# USBDUINO_DIP_SCH.net
KiCad netlist of a schematic drawn in EAGLE
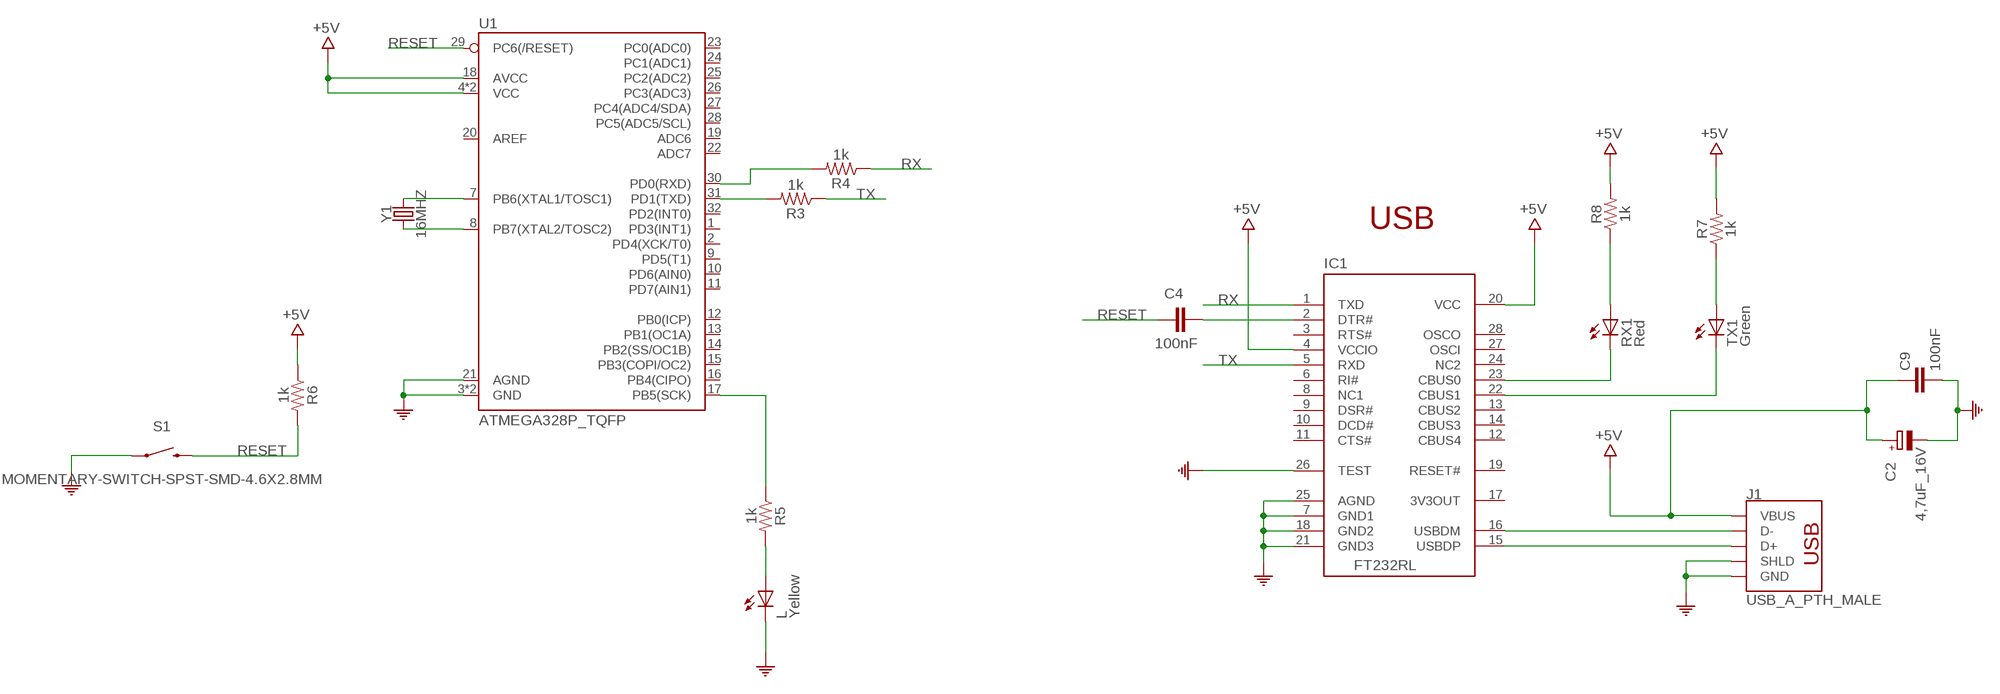
[diagram p0: schematic, sheet 1]

(export (version "E")
  (design (tool "Eeschema 10.0.6"))
  (components
    (comp (ref "C2")
      (value "4,7uF_16V")
      (footprint "eagle-import:TAN-A")
      (fields (field (name "PART_NUMBER") "TAJA475MO16RNJ"))
      (libsource (lib "eagle-import") (part "0833_TAJA475MO16RNJ"))
    )
    (comp (ref "C4")
      (value "100nF")
      (footprint "eagle-import:C0603-ROUND")
      (fields (field (name "PART_NUMBER") "cl10b104kbnc"))
      (libsource (lib "eagle-import") (part "0015_100NF_0603"))
    )
    (comp (ref "C9")
      (value "100nF")
      (footprint "eagle-import:C0603-ROUND")
      (fields (field (name "PART_NUMBER") "cl10b104kbnc"))
      (libsource (lib "eagle-import") (part "0015_100NF_0603"))
    )
    (comp (ref "IC1")
      (value "FT232RL")
      (footprint "eagle-import:SSOP28")
      (libsource (lib "eagle-import") (part "0226_FT232RL"))
    )
    (comp (ref "J1")
      (value "USB_A_PTH_MALE")
      (footprint "eagle-import:USB-A-H")
      (libsource (lib "eagle-import") (part "USB_A_PTH_MALE"))
    )
    (comp (ref "L")
      (value "Yellow")
      (footprint "eagle-import:CHIPLED_0805")
      (fields (field (name "PART_NUMBER") "KPT-2012YC"))
      (libsource (lib "eagle-import") (part "0044_KPT-2012YC"))
    )
    (comp (ref "R3")
      (value "1k")
      (footprint "eagle-import:0603")
      (libsource (lib "eagle-import") (part "1KOHM-0603-1/10W-1%"))
    )
    (comp (ref "R4")
      (value "1k")
      (footprint "eagle-import:0603")
      (libsource (lib "eagle-import") (part "1KOHM-0603-1/10W-1%"))
    )
    (comp (ref "R5")
      (value "1k")
      (footprint "eagle-import:0603")
      (libsource (lib "eagle-import") (part "1KOHM-0603-1/10W-1%"))
    )
    (comp (ref "R6")
      (value "1k")
      (footprint "eagle-import:0603")
      (libsource (lib "eagle-import") (part "1KOHM-0603-1/10W-1%"))
    )
    (comp (ref "R7")
      (value "1k")
      (footprint "eagle-import:0603")
      (libsource (lib "eagle-import") (part "1KOHM-0603-1/10W-1%"))
    )
    (comp (ref "R8")
      (value "1k")
      (footprint "eagle-import:0603")
      (libsource (lib "eagle-import") (part "1KOHM-0603-1/10W-1%"))
    )
    (comp (ref "RX1")
      (value "Red")
      (footprint "eagle-import:CHIPLED_0805")
      (fields (field (name "PART_NUMBER") "KTP-2012SURCK"))
      (libsource (lib "eagle-import") (part "0181_KTP-2012SURCK"))
    )
    (comp (ref "S1")
      (value "MOMENTARY-SWITCH-SPST-SMD-4.6X2.8MM")
      (footprint "eagle-import:TACTILE_SWITCH_SMD_4.6X2.8MM")
      (libsource (lib "eagle-import") (part "MOMENTARY-SWITCH-SPST-SMD-4.6X2.8MM"))
    )
    (comp (ref "TX1")
      (value "Green")
      (footprint "eagle-import:CHIPLED_0805")
      (fields (field (name "PART_NUMBER") "KPT-2012SGC"))
      (libsource (lib "eagle-import") (part "0043_KPT-2012SGC"))
    )
    (comp (ref "U1")
      (value "ATMEGA328P_TQFP")
      (footprint "eagle-import:TQFP32-08")
      (libsource (lib "eagle-import") (part "ATMEGA328P_TQFP"))
    )
    (comp (ref "Y1")
      (value "16MHZ")
      (footprint "eagle-import:HC49UP")
      (libsource (lib "eagle-import") (part "CRYSTALSMD-HC49UP"))
    )
  )
  (nets
    (net (code "1") (name "+5V") (class "Default")
      (node (ref "C2") (pin "1") (pinfunction "+_1") (pintype "passive"))
      (node (ref "C9") (pin "1") (pinfunction "1_1") (pintype "passive"))
      (node (ref "IC1") (pin "20") (pinfunction "VCC_20") (pintype "power_in"))
      (node (ref "IC1") (pin "4") (pinfunction "VCCIO_4") (pintype "power_in"))
      (node (ref "J1") (pin "VBUS") (pinfunction "VBUS_VBUS") (pintype "power_in"))
      (node (ref "R6") (pin "1") (pinfunction "1_1") (pintype "passive"))
      (node (ref "R7") (pin "2") (pinfunction "2_2") (pintype "passive"))
      (node (ref "R8") (pin "2") (pinfunction "2_2") (pintype "passive"))
      (node (ref "U1") (pin "18") (pinfunction "AVCC_18") (pintype "bidirectional"))
      (node (ref "U1") (pin "4") (pinfunction "VCC_4") (pintype "bidirectional"))
      (node (ref "U1") (pin "6") (pinfunction "VCC_6") (pintype "bidirectional"))
    )
    (net (code "2") (name "/3V3OUT") (class "Default")
      (node (ref "IC1") (pin "17") (pinfunction "3V3OUT_17") (pintype "power_in"))
    )
    (net (code "3") (name "/RESET") (class "Default")
      (node (ref "C4") (pin "1") (pinfunction "1_1") (pintype "passive"))
      (node (ref "R6") (pin "2") (pinfunction "2_2") (pintype "passive"))
      (node (ref "S1") (pin "3") (pinfunction "2_3") (pintype "passive"))
      (node (ref "S1") (pin "4") (pinfunction "2_4") (pintype "passive"))
      (node (ref "U1") (pin "29") (pinfunction "PC6(/RESET)_29") (pintype "bidirectional"))
    )
    (net (code "4") (name "/RX") (class "Default")
      (node (ref "IC1") (pin "1") (pinfunction "TXD_1") (pintype "output"))
      (node (ref "R4") (pin "1") (pinfunction "1_1") (pintype "passive"))
    )
    (net (code "5") (name "/TX") (class "Default")
      (node (ref "IC1") (pin "5") (pinfunction "RXD_5") (pintype "input"))
      (node (ref "R3") (pin "1") (pinfunction "1_1") (pintype "passive"))
    )
    (net (code "6") (name "COM") (class "Default")
      (node (ref "C2") (pin "2") (pinfunction "-_2") (pintype "passive"))
      (node (ref "C9") (pin "2") (pinfunction "2_2") (pintype "passive"))
      (node (ref "IC1") (pin "18") (pinfunction "GND2_18") (pintype "power_in"))
      (node (ref "IC1") (pin "21") (pinfunction "GND3_21") (pintype "power_in"))
      (node (ref "IC1") (pin "25") (pinfunction "AGND_25") (pintype "power_in"))
      (node (ref "IC1") (pin "26") (pinfunction "TEST_26") (pintype "bidirectional"))
      (node (ref "IC1") (pin "7") (pinfunction "GND1_7") (pintype "power_in"))
      (node (ref "J1") (pin "GND") (pinfunction "GND_GND") (pintype "power_in"))
      (node (ref "J1") (pin "SHLD1") (pinfunction "SHLD_SHLD1") (pintype "bidirectional"))
      (node (ref "J1") (pin "SHLD2") (pinfunction "SHLD_SHLD2") (pintype "bidirectional"))
      (node (ref "L") (pin "C") (pinfunction "C_C") (pintype "passive"))
      (node (ref "S1") (pin "1") (pinfunction "1_1") (pintype "passive"))
      (node (ref "S1") (pin "2") (pinfunction "1_2") (pintype "passive"))
      (node (ref "U1") (pin "21") (pinfunction "AGND_21") (pintype "bidirectional"))
      (node (ref "U1") (pin "3") (pinfunction "GND_3") (pintype "bidirectional"))
      (node (ref "U1") (pin "5") (pinfunction "GND_5") (pintype "bidirectional"))
    )
    (net (code "7") (name "Net-(IC1-CBUS0)") (class "Default")
      (node (ref "IC1") (pin "23") (pinfunction "CBUS0_23") (pintype "bidirectional"))
      (node (ref "RX1") (pin "C") (pinfunction "C_C") (pintype "passive"))
    )
    (net (code "8") (name "Net-(IC1-CBUS1)") (class "Default")
      (node (ref "IC1") (pin "22") (pinfunction "CBUS1_22") (pintype "bidirectional"))
      (node (ref "TX1") (pin "C") (pinfunction "C_C") (pintype "passive"))
    )
    (net (code "9") (name "Net-(IC1-DTR#)") (class "Default")
      (node (ref "C4") (pin "2") (pinfunction "2_2") (pintype "passive"))
      (node (ref "IC1") (pin "2") (pinfunction "DTR#_2") (pintype "output"))
    )
    (net (code "10") (name "Net-(IC1-USBDM)") (class "Default")
      (node (ref "IC1") (pin "16") (pinfunction "USBDM_16") (pintype "bidirectional"))
      (node (ref "J1") (pin "D-") (pinfunction "D-_D-") (pintype "bidirectional"))
    )
    (net (code "11") (name "Net-(IC1-USBDP)") (class "Default")
      (node (ref "IC1") (pin "15") (pinfunction "USBDP_15") (pintype "bidirectional"))
      (node (ref "J1") (pin "D+") (pinfunction "D+_D+") (pintype "bidirectional"))
    )
    (net (code "12") (name "Net-(L-PadA)") (class "Default")
      (node (ref "L") (pin "A") (pinfunction "A_A") (pintype "passive"))
      (node (ref "R5") (pin "2") (pinfunction "2_2") (pintype "passive"))
    )
    (net (code "13") (name "Net-(R7-Pad1)") (class "Default")
      (node (ref "R7") (pin "1") (pinfunction "1_1") (pintype "passive"))
      (node (ref "TX1") (pin "A") (pinfunction "A_A") (pintype "passive"))
    )
    (net (code "14") (name "Net-(R8-Pad1)") (class "Default")
      (node (ref "R8") (pin "1") (pinfunction "1_1") (pintype "passive"))
      (node (ref "RX1") (pin "A") (pinfunction "A_A") (pintype "passive"))
    )
    (net (code "15") (name "Net-(U1-PB5(SCK))") (class "Default")
      (node (ref "R5") (pin "1") (pinfunction "1_1") (pintype "passive"))
      (node (ref "U1") (pin "17") (pinfunction "PB5(SCK)_17") (pintype "bidirectional"))
    )
    (net (code "16") (name "Net-(U1-PB6(XTAL1{slash}TOSC1))") (class "Default")
      (node (ref "U1") (pin "7") (pinfunction "PB6(XTAL1/TOSC1)_7") (pintype "bidirectional"))
      (node (ref "Y1") (pin "2") (pinfunction "2_2") (pintype "passive"))
    )
    (net (code "17") (name "Net-(U1-PB7(XTAL2{slash}TOSC2))") (class "Default")
      (node (ref "U1") (pin "8") (pinfunction "PB7(XTAL2/TOSC2)_8") (pintype "bidirectional"))
      (node (ref "Y1") (pin "1") (pinfunction "1_1") (pintype "passive"))
    )
    (net (code "18") (name "Net-(U1-PD0(RXD))") (class "Default")
      (node (ref "R4") (pin "2") (pinfunction "2_2") (pintype "passive"))
      (node (ref "U1") (pin "30") (pinfunction "PD0(RXD)_30") (pintype "bidirectional"))
    )
    (net (code "19") (name "Net-(U1-PD1(TXD))") (class "Default")
      (node (ref "R3") (pin "2") (pinfunction "2_2") (pintype "passive"))
      (node (ref "U1") (pin "31") (pinfunction "PD1(TXD)_31") (pintype "bidirectional"))
    )
    (net (code "20") (name "unconnected-(IC1-CBUS2-Pad13)") (class "Default")
      (node (ref "IC1") (pin "13") (pinfunction "CBUS2_13") (pintype "bidirectional"))
    )
    (net (code "21") (name "unconnected-(IC1-CBUS3-Pad14)") (class "Default")
      (node (ref "IC1") (pin "14") (pinfunction "CBUS3_14") (pintype "bidirectional"))
    )
    (net (code "22") (name "unconnected-(IC1-CBUS4-Pad12)") (class "Default")
      (node (ref "IC1") (pin "12") (pinfunction "CBUS4_12") (pintype "bidirectional"))
    )
    (net (code "23") (name "unconnected-(IC1-CTS#-Pad11)") (class "Default")
      (node (ref "IC1") (pin "11") (pinfunction "CTS#_11") (pintype "bidirectional"))
    )
    (net (code "24") (name "unconnected-(IC1-DCD#-Pad10)") (class "Default")
      (node (ref "IC1") (pin "10") (pinfunction "DCD#_10") (pintype "bidirectional"))
    )
    (net (code "25") (name "unconnected-(IC1-DSR#-Pad9)") (class "Default")
      (node (ref "IC1") (pin "9") (pinfunction "DSR#_9") (pintype "bidirectional"))
    )
    (net (code "26") (name "unconnected-(IC1-NC1-Pad8)") (class "Default")
      (node (ref "IC1") (pin "8") (pinfunction "NC1_8") (pintype "bidirectional"))
    )
    (net (code "27") (name "unconnected-(IC1-NC2-Pad24)") (class "Default")
      (node (ref "IC1") (pin "24") (pinfunction "NC2_24") (pintype "no_connect"))
    )
    (net (code "28") (name "unconnected-(IC1-OSCI-Pad27)") (class "Default")
      (node (ref "IC1") (pin "27") (pinfunction "OSCI_27") (pintype "bidirectional"))
    )
    (net (code "29") (name "unconnected-(IC1-OSCO-Pad28)") (class "Default")
      (node (ref "IC1") (pin "28") (pinfunction "OSCO_28") (pintype "output"))
    )
    (net (code "30") (name "unconnected-(IC1-RESET#-Pad19)") (class "Default")
      (node (ref "IC1") (pin "19") (pinfunction "RESET#_19") (pintype "bidirectional"))
    )
    (net (code "31") (name "unconnected-(IC1-RI#-Pad6)") (class "Default")
      (node (ref "IC1") (pin "6") (pinfunction "RI#_6") (pintype "bidirectional"))
    )
    (net (code "32") (name "unconnected-(IC1-RTS#-Pad3)") (class "Default")
      (node (ref "IC1") (pin "3") (pinfunction "RTS#_3") (pintype "output"))
    )
    (net (code "33") (name "unconnected-(U1-ADC6-Pad19)") (class "Default")
      (node (ref "U1") (pin "19") (pinfunction "ADC6_19") (pintype "bidirectional"))
    )
    (net (code "34") (name "unconnected-(U1-ADC7-Pad22)") (class "Default")
      (node (ref "U1") (pin "22") (pinfunction "ADC7_22") (pintype "bidirectional"))
    )
    (net (code "35") (name "unconnected-(U1-AREF-Pad20)") (class "Default")
      (node (ref "U1") (pin "20") (pinfunction "AREF_20") (pintype "bidirectional"))
    )
    (net (code "36") (name "unconnected-(U1-PB0(ICP)-Pad12)") (class "Default")
      (node (ref "U1") (pin "12") (pinfunction "PB0(ICP)_12") (pintype "bidirectional"))
    )
    (net (code "37") (name "unconnected-(U1-PB1(OC1A)-Pad13)") (class "Default")
      (node (ref "U1") (pin "13") (pinfunction "PB1(OC1A)_13") (pintype "bidirectional"))
    )
    (net (code "38") (name "unconnected-(U1-PB2(SS{slash}OC1B)-Pad14)") (class "Default")
      (node (ref "U1") (pin "14") (pinfunction "PB2(SS/OC1B)_14") (pintype "bidirectional"))
    )
    (net (code "39") (name "unconnected-(U1-PB3(COPI{slash}OC2)-Pad15)") (class "Default")
      (node (ref "U1") (pin "15") (pinfunction "PB3(COPI/OC2)_15") (pintype "bidirectional"))
    )
    (net (code "40") (name "unconnected-(U1-PB4(CIPO)-Pad16)") (class "Default")
      (node (ref "U1") (pin "16") (pinfunction "PB4(CIPO)_16") (pintype "bidirectional"))
    )
    (net (code "41") (name "unconnected-(U1-PC0(ADC0)-Pad23)") (class "Default")
      (node (ref "U1") (pin "23") (pinfunction "PC0(ADC0)_23") (pintype "bidirectional"))
    )
    (net (code "42") (name "unconnected-(U1-PC1(ADC1)-Pad24)") (class "Default")
      (node (ref "U1") (pin "24") (pinfunction "PC1(ADC1)_24") (pintype "bidirectional"))
    )
    (net (code "43") (name "unconnected-(U1-PC2(ADC2)-Pad25)") (class "Default")
      (node (ref "U1") (pin "25") (pinfunction "PC2(ADC2)_25") (pintype "bidirectional"))
    )
    (net (code "44") (name "unconnected-(U1-PC3(ADC3)-Pad26)") (class "Default")
      (node (ref "U1") (pin "26") (pinfunction "PC3(ADC3)_26") (pintype "bidirectional"))
    )
    (net (code "45") (name "unconnected-(U1-PC4(ADC4{slash}SDA)-Pad27)") (class "Default")
      (node (ref "U1") (pin "27") (pinfunction "PC4(ADC4/SDA)_27") (pintype "bidirectional"))
    )
    (net (code "46") (name "unconnected-(U1-PC5(ADC5{slash}SCL)-Pad28)") (class "Default")
      (node (ref "U1") (pin "28") (pinfunction "PC5(ADC5/SCL)_28") (pintype "bidirectional"))
    )
    (net (code "47") (name "unconnected-(U1-PD2(INT0)-Pad32)") (class "Default")
      (node (ref "U1") (pin "32") (pinfunction "PD2(INT0)_32") (pintype "bidirectional"))
    )
    (net (code "48") (name "unconnected-(U1-PD3(INT1)-Pad1)") (class "Default")
      (node (ref "U1") (pin "1") (pinfunction "PD3(INT1)_1") (pintype "bidirectional"))
    )
    (net (code "49") (name "unconnected-(U1-PD4(XCK{slash}T0)-Pad2)") (class "Default")
      (node (ref "U1") (pin "2") (pinfunction "PD4(XCK/T0)_2") (pintype "bidirectional"))
    )
    (net (code "50") (name "unconnected-(U1-PD5(T1)-Pad9)") (class "Default")
      (node (ref "U1") (pin "9") (pinfunction "PD5(T1)_9") (pintype "bidirectional"))
    )
    (net (code "51") (name "unconnected-(U1-PD6(AIN0)-Pad10)") (class "Default")
      (node (ref "U1") (pin "10") (pinfunction "PD6(AIN0)_10") (pintype "bidirectional"))
    )
    (net (code "52") (name "unconnected-(U1-PD7(AIN1)-Pad11)") (class "Default")
      (node (ref "U1") (pin "11") (pinfunction "PD7(AIN1)_11") (pintype "bidirectional"))
    )
  )
)
